# ethernet.net
KiCad netlist of a schematic drawn in Altium Designer
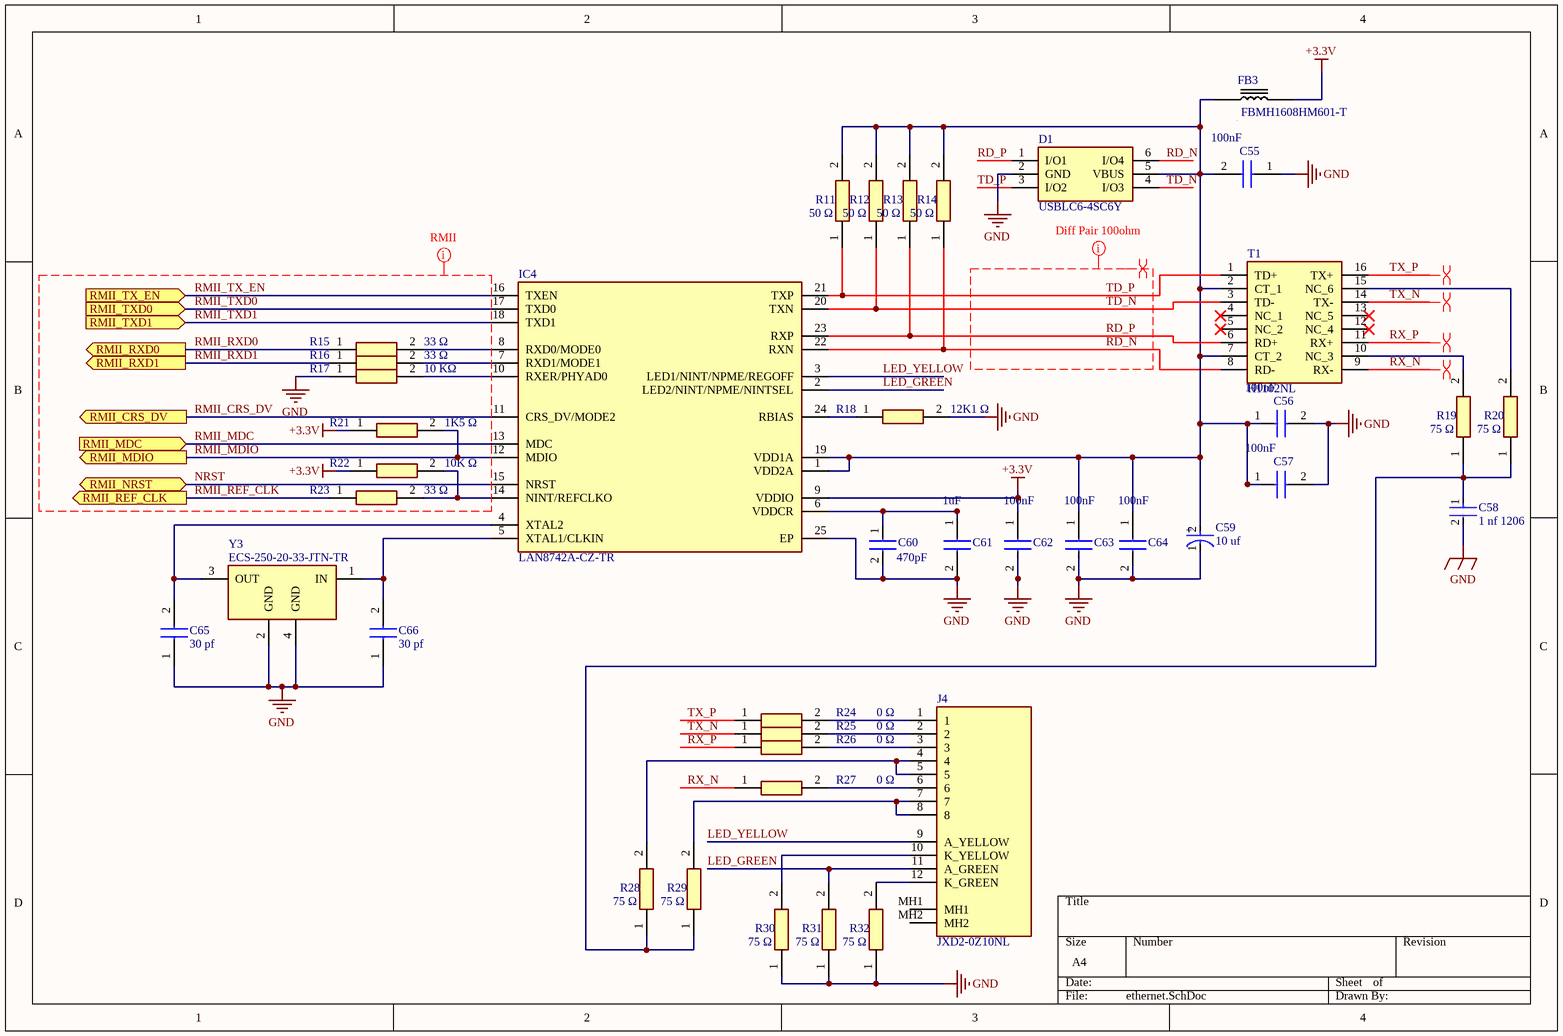
[diagram p0: ethernet.SchDoc]

(export (version "E")
  (design (tool "Eeschema 10.0.6"))
  (components
    (comp (ref "C55")
      (value "100nF")
      (footprint "PCB_library:CAPC1608X87N")
      (fields
        (field (name "MANUFACTURER_PART_NUMBER") "C0603C300J5GACTU")
        (field (name "MOUSER PART NUMBER") "80-C0603C300J5G")
        (field (name "MANUFACTURER") "TDK")
      )
      (libsource (lib "PCB_library") (part "C0603C300J5GACTU"))
    )
    (comp (ref "C56")
      (value "100nF")
      (footprint "PCB_library:CAPC1608X87N")
      (fields
        (field (name "MANUFACTURER_PART_NUMBER") "C0603C300J5GACTU")
        (field (name "MOUSER PART NUMBER") "80-C0603C300J5G")
        (field (name "MANUFACTURER") "TDK")
      )
      (libsource (lib "PCB_library") (part "C0603C300J5GACTU"))
    )
    (comp (ref "C57")
      (value "100nF")
      (footprint "PCB_library:CAPC1608X87N")
      (fields
        (field (name "MANUFACTURER_PART_NUMBER") "C0603C300J5GACTU")
        (field (name "MOUSER PART NUMBER") "80-C0603C300J5G")
        (field (name "MANUFACTURER") "TDK")
      )
      (libsource (lib "PCB_library") (part "C0603C300J5GACTU"))
    )
    (comp (ref "C58")
      (value "1 nf 1206")
      (footprint "FP-CC1206-0_3-1_45-IPC_C")
      (description "CAP CER 1000PF 2KV X7R 1206")
      (fields (field (name "TOLERANCE") "10%") (field (name "VOLTAGE") "2kV"))
      (libsource (lib "Altium Content Vault") (part "02cd4be3c70576c341d710602a673aa"))
    )
    (comp (ref "C59")
      (value "10 uf")
      (footprint "FP-T491D-MFG")
      (description "CAP TANT 10UF 10% 25V 2917")
      (fields (field (name "VOLTAGE") "25V") (field (name "TOLERANCE") "20%"))
      (libsource (lib "Altium Content Vault") (part "cf48714ba7e38822c1575c7ec0b6d1f"))
    )
    (comp (ref "C60")
      (value "470pF")
      (footprint "PCB_library:CAPC1005X55N")
      (fields
        (field (name "MANUFACTURER_PART_NUMBER") "CC0402KRX7R7BB104")
        (field (name "MOUSER PART NUMBER") "603-CC402KRX7R7BB104")
        (field (name "MANUFACTURER") "Murata")
      )
      (libsource (lib "PCB_library") (part "CC0402KRX7R7BB104"))
    )
    (comp (ref "C61")
      (value "1uF")
      (footprint "PCB_library:CAPC1608X87N")
      (fields
        (field (name "MANUFACTURER_PART_NUMBER") "C0603C300J5GACTU")
        (field (name "MOUSER PART NUMBER") "80-C0603C300J5G")
        (field (name "MANUFACTURER") "Kyocera AVX")
      )
      (libsource (lib "PCB_library") (part "C0603C300J5GACTU"))
    )
    (comp (ref "C62")
      (value "100nF")
      (footprint "PCB_library:CAPC1608X87N")
      (fields
        (field (name "MANUFACTURER_PART_NUMBER") "C0603C300J5GACTU")
        (field (name "MOUSER PART NUMBER") "80-C0603C300J5G")
        (field (name "MANUFACTURER") "TDK")
      )
      (libsource (lib "PCB_library") (part "C0603C300J5GACTU"))
    )
    (comp (ref "C63")
      (value "100nF")
      (footprint "PCB_library:CAPC1608X87N")
      (fields
        (field (name "MANUFACTURER_PART_NUMBER") "C0603C300J5GACTU")
        (field (name "MOUSER PART NUMBER") "80-C0603C300J5G")
        (field (name "MANUFACTURER") "TDK")
      )
      (libsource (lib "PCB_library") (part "C0603C300J5GACTU"))
    )
    (comp (ref "C64")
      (value "100nF")
      (footprint "PCB_library:CAPC1608X87N")
      (fields
        (field (name "MANUFACTURER_PART_NUMBER") "C0603C300J5GACTU")
        (field (name "MOUSER PART NUMBER") "80-C0603C300J5G")
        (field (name "MANUFACTURER") "TDK")
      )
      (libsource (lib "PCB_library") (part "C0603C300J5GACTU"))
    )
    (comp (ref "C65")
      (value "30 pf")
      (footprint "PCB_library:CAPC1608X87N")
      (fields
        (field (name "MANUFACTURER_PART_NUMBER") "C0603C300J5GACTU")
        (field (name "MOUSER PART NUMBER") "80-C0603C300J5G")
        (field (name "MANUFACTURER") "KEMET")
      )
      (libsource (lib "*") (part "C0603C300J5GACTU"))
    )
    (comp (ref "C66")
      (value "30 pf")
      (footprint "PCB_library:CAPC1608X87N")
      (fields
        (field (name "MANUFACTURER_PART_NUMBER") "C0603C300J5GACTU")
        (field (name "MOUSER PART NUMBER") "80-C0603C300J5G")
        (field (name "MANUFACTURER") "KEMET")
      )
      (libsource (lib "*") (part "C0603C300J5GACTU"))
    )
    (comp (ref "D1")
      (value "USBLC6-4SC6Y")
      (footprint "PCB_library:SOT95P280X145-6N")
      (description "Diode ESD (Uni-directional)")
      (fields (field (name "MOUSER PART NUMBER") "511-USBLC6-4SC6Y"))
      (libsource (lib "*") (part "USBLC6-4SC6Y"))
    )
    (comp (ref "FB3")
      (value "FBMH1608HM601-T")
      (footprint "PCB_library:BEADC1608X90N")
      (description "Ferrite Bead")
      (fields (field (name "MOUSER PART NUMBER") "963-FBMH1608HM601-T"))
      (libsource (lib "PCB_library") (part "FBMH1608HM601-T"))
    )
    (comp (ref "IC4")
      (value "LAN8742A-CZ-TR")
      (footprint "PCB_library:QFN50P400X400X100-25N-D")
      (description "Integrated Circuit")
      (fields (field (name "MOUSER PART NUMBER") "579-LAN8742A-CZ-TR"))
      (libsource (lib "PCB_library") (part "LAN8742A-CZ-TR"))
    )
    (comp (ref "J4")
      (value "JXD2-0Z10NL")
      (footprint "PCB_library:JXD20Z10NL")
      (description "Conn Jack 1PORT 100 Base-tx Pcb")
      (fields (field (name "MOUSER PART NUMBER") "673-JXD2-0Z10NL") (field (name "MANUFACTURER") "Pulse"))
      (libsource (lib "PCB_library") (part "JXD2-0Z10NL"))
    )
    (comp (ref "R11")
      (value "50 Ω")
      (footprint "RESC1005X35N")
      (description "Resistor")
      (fields
        (field (name "MANUFACTURER_PART_NUMBER") "CPF0402B100KE")
        (field (name "MOUSER PART NUMBER") "279-CPF0402B100KE")
      )
      (libsource (lib "*") (part "CPF0402B100KE"))
    )
    (comp (ref "R12")
      (value "50 Ω")
      (footprint "RESC1005X35N")
      (description "Resistor")
      (fields
        (field (name "MANUFACTURER_PART_NUMBER") "CPF0402B100KE")
        (field (name "MOUSER PART NUMBER") "279-CPF0402B100KE")
      )
      (libsource (lib "*") (part "CPF0402B100KE"))
    )
    (comp (ref "R13")
      (value "50 Ω")
      (footprint "RESC1005X35N")
      (description "Resistor")
      (fields
        (field (name "MANUFACTURER_PART_NUMBER") "CPF0402B100KE")
        (field (name "MOUSER PART NUMBER") "279-CPF0402B100KE")
      )
      (libsource (lib "*") (part "CPF0402B100KE"))
    )
    (comp (ref "R14")
      (value "50 Ω")
      (footprint "RESC1005X35N")
      (description "Resistor")
      (fields
        (field (name "MANUFACTURER_PART_NUMBER") "CPF0402B100KE")
        (field (name "MOUSER PART NUMBER") "279-CPF0402B100KE")
      )
      (libsource (lib "*") (part "CPF0402B100KE"))
    )
    (comp (ref "R15")
      (value "33 Ω")
      (footprint "RESC1005X35N")
      (description "Resistor")
      (fields
        (field (name "MANUFACTURER_PART_NUMBER") "CPF0402B100KE")
        (field (name "MOUSER PART NUMBER") "279-CPF0402B100KE")
      )
      (libsource (lib "") (part "CPF0402B100KE_1"))
    )
    (comp (ref "R16")
      (value "33 Ω")
      (footprint "RESC1005X35N")
      (description "Resistor")
      (fields
        (field (name "MANUFACTURER_PART_NUMBER") "CPF0402B100KE")
        (field (name "MOUSER PART NUMBER") "279-CPF0402B100KE")
      )
      (libsource (lib "") (part "CPF0402B100KE_1"))
    )
    (comp (ref "R17")
      (value "10 KΩ")
      (footprint "RESC1005X35N")
      (description "Resistor")
      (fields
        (field (name "MANUFACTURER_PART_NUMBER") "CPF0402B100KE")
        (field (name "MOUSER PART NUMBER") "279-CPF0402B100KE")
      )
      (libsource (lib "") (part "CPF0402B100KE_1"))
    )
    (comp (ref "R18")
      (value "12K1 Ω")
      (footprint "RESC1005X35N")
      (description "Resistor")
      (fields
        (field (name "MANUFACTURER_PART_NUMBER") "CPF0402B100KE")
        (field (name "MOUSER PART NUMBER") "279-CPF0402B100KE")
      )
      (libsource (lib "") (part "CPF0402B100KE_1"))
    )
    (comp (ref "R19")
      (value "75 Ω")
      (footprint "RESC1005X35N")
      (description "Resistor")
      (fields
        (field (name "MANUFACTURER_PART_NUMBER") "CPF0402B100KE")
        (field (name "MOUSER PART NUMBER") "279-CPF0402B100KE")
      )
      (libsource (lib "*") (part "CPF0402B100KE"))
    )
    (comp (ref "R20")
      (value "75 Ω")
      (footprint "RESC1005X35N")
      (description "Resistor")
      (fields
        (field (name "MANUFACTURER_PART_NUMBER") "CPF0402B100KE")
        (field (name "MOUSER PART NUMBER") "279-CPF0402B100KE")
      )
      (libsource (lib "*") (part "CPF0402B100KE"))
    )
    (comp (ref "R21")
      (value "1K5 Ω")
      (footprint "RESC1005X35N")
      (description "Resistor")
      (fields
        (field (name "MANUFACTURER_PART_NUMBER") "CPF0402B100KE")
        (field (name "MOUSER PART NUMBER") "279-CPF0402B100KE")
      )
      (libsource (lib "") (part "CPF0402B100KE_1"))
    )
    (comp (ref "R22")
      (value "10K Ω")
      (footprint "RESC1005X35N")
      (description "Resistor")
      (fields
        (field (name "MANUFACTURER_PART_NUMBER") "CPF0402B100KE")
        (field (name "MOUSER PART NUMBER") "279-CPF0402B100KE")
      )
      (libsource (lib "") (part "CPF0402B100KE_1"))
    )
    (comp (ref "R23")
      (value "33 Ω")
      (footprint "RESC1005X35N")
      (description "Resistor")
      (fields
        (field (name "MANUFACTURER_PART_NUMBER") "CPF0402B100KE")
        (field (name "MOUSER PART NUMBER") "279-CPF0402B100KE")
      )
      (libsource (lib "") (part "CPF0402B100KE_1"))
    )
    (comp (ref "R24")
      (value "0 Ω")
      (footprint "RESC1005X35N")
      (description "Resistor")
      (fields
        (field (name "MANUFACTURER_PART_NUMBER") "CPF0402B100KE")
        (field (name "MOUSER PART NUMBER") "279-CPF0402B100KE")
      )
      (libsource (lib "") (part "CPF0402B100KE_1"))
    )
    (comp (ref "R25")
      (value "0 Ω")
      (footprint "RESC1005X35N")
      (description "Resistor")
      (fields
        (field (name "MANUFACTURER_PART_NUMBER") "CPF0402B100KE")
        (field (name "MOUSER PART NUMBER") "279-CPF0402B100KE")
      )
      (libsource (lib "") (part "CPF0402B100KE_1"))
    )
    (comp (ref "R26")
      (value "0 Ω")
      (footprint "RESC1005X35N")
      (description "Resistor")
      (fields
        (field (name "MANUFACTURER_PART_NUMBER") "CPF0402B100KE")
        (field (name "MOUSER PART NUMBER") "279-CPF0402B100KE")
      )
      (libsource (lib "") (part "CPF0402B100KE_1"))
    )
    (comp (ref "R27")
      (value "0 Ω")
      (footprint "RESC1005X35N")
      (description "Resistor")
      (fields
        (field (name "MANUFACTURER_PART_NUMBER") "CPF0402B100KE")
        (field (name "MOUSER PART NUMBER") "279-CPF0402B100KE")
      )
      (libsource (lib "") (part "CPF0402B100KE_1"))
    )
    (comp (ref "R28")
      (value "75 Ω")
      (footprint "RESC1005X35N")
      (description "Resistor")
      (fields
        (field (name "MANUFACTURER_PART_NUMBER") "CPF0402B100KE")
        (field (name "MOUSER PART NUMBER") "279-CPF0402B100KE")
      )
      (libsource (lib "*") (part "CPF0402B100KE"))
    )
    (comp (ref "R29")
      (value "75 Ω")
      (footprint "RESC1005X35N")
      (description "Resistor")
      (fields
        (field (name "MANUFACTURER_PART_NUMBER") "CPF0402B100KE")
        (field (name "MOUSER PART NUMBER") "279-CPF0402B100KE")
      )
      (libsource (lib "*") (part "CPF0402B100KE"))
    )
    (comp (ref "R30")
      (value "75 Ω")
      (footprint "RESC1005X35N")
      (description "Resistor")
      (fields
        (field (name "MANUFACTURER_PART_NUMBER") "CPF0402B100KE")
        (field (name "MOUSER PART NUMBER") "279-CPF0402B100KE")
      )
      (libsource (lib "*") (part "CPF0402B100KE"))
    )
    (comp (ref "R31")
      (value "75 Ω")
      (footprint "RESC1005X35N")
      (description "Resistor")
      (fields
        (field (name "MANUFACTURER_PART_NUMBER") "CPF0402B100KE")
        (field (name "MOUSER PART NUMBER") "279-CPF0402B100KE")
      )
      (libsource (lib "*") (part "CPF0402B100KE"))
    )
    (comp (ref "R32")
      (value "75 Ω")
      (footprint "RESC1005X35N")
      (description "Resistor")
      (fields
        (field (name "MANUFACTURER_PART_NUMBER") "CPF0402B100KE")
        (field (name "MOUSER PART NUMBER") "279-CPF0402B100KE")
      )
      (libsource (lib "*") (part "CPF0402B100KE"))
    )
    (comp (ref "T1")
      (value "H1102NL")
      (footprint "PCB_library:SOIC127P940X597-16N")
      (description "Transformer")
      (fields (field (name "MOUSER PART NUMBER") "673-H1102NL"))
      (libsource (lib "*") (part "H1102NL"))
    )
    (comp (ref "Y3")
      (value "ECS-250-20-33-JTN-TR")
      (footprint "ECS-250-20-33-JTN-TR")
      (description "Crystal or Oscillator")
      (fields (field (name "MANUFACTURER_PART_NUMBER") "CO4605-100.000-T-TR"))
      (libsource (lib "PCB_library") (part "ECS-250-20-33-JTN-TR"))
    )
  )
  (nets
    (net (code "1") (name "+3.3V") (class "Default")
      (node (ref "C62") (pin "1") (pinfunction "1_1") (pintype "passive"))
      (node (ref "FB3") (pin "2") (pinfunction "2_2") (pintype "passive"))
      (node (ref "IC4") (pin "9") (pinfunction "VDDIO_9") (pintype "passive"))
      (node (ref "R21") (pin "1") (pinfunction "1_1") (pintype "passive"))
      (node (ref "R22") (pin "1") (pinfunction "1_1") (pintype "passive"))
    )
    (net (code "2") (name "/LED_GREEN") (class "Default")
      (node (ref "IC4") (pin "2") (pinfunction "LED2/NINT/NPME/NINTSEL_2") (pintype "passive"))
      (node (ref "J4") (pin "11") (pinfunction "A_GREEN_11") (pintype "passive"))
      (node (ref "R31") (pin "2") (pinfunction "2_2") (pintype "passive"))
    )
    (net (code "3") (name "/LED_YELLOW") (class "Default")
      (node (ref "IC4") (pin "3") (pinfunction "LED1/NINT/NPME/REGOFF_3") (pintype "passive"))
      (node (ref "J4") (pin "9") (pinfunction "A_YELLOW_9") (pintype "passive"))
    )
    (net (code "4") (name "/NRST") (class "Default")
      (node (ref "IC4") (pin "15") (pinfunction "NRST_15") (pintype "passive"))
    )
    (net (code "5") (name "/RD_N") (class "Default")
      (node (ref "D1") (pin "6") (pinfunction "I/O4_6") (pintype "passive"))
      (node (ref "IC4") (pin "22") (pinfunction "RXN_22") (pintype "passive"))
      (node (ref "R14") (pin "1") (pinfunction "1_1") (pintype "passive"))
      (node (ref "T1") (pin "8") (pinfunction "RD-_8") (pintype "passive"))
    )
    (net (code "6") (name "/RD_P") (class "Default")
      (node (ref "D1") (pin "1") (pinfunction "I/O1_1") (pintype "passive"))
      (node (ref "IC4") (pin "23") (pinfunction "RXP_23") (pintype "passive"))
      (node (ref "R13") (pin "1") (pinfunction "1_1") (pintype "passive"))
      (node (ref "T1") (pin "6") (pinfunction "RD+_6") (pintype "passive"))
    )
    (net (code "7") (name "/RMII_CRS_DV") (class "Default")
      (node (ref "IC4") (pin "11") (pinfunction "CRS_DV/MODE2_11") (pintype "passive"))
    )
    (net (code "8") (name "/RMII_MDC") (class "Default")
      (node (ref "IC4") (pin "13") (pinfunction "MDC_13") (pintype "passive"))
    )
    (net (code "9") (name "/RMII_MDIO") (class "Default")
      (node (ref "IC4") (pin "12") (pinfunction "MDIO_12") (pintype "passive"))
      (node (ref "R21") (pin "2") (pinfunction "2_2") (pintype "passive"))
    )
    (net (code "10") (name "/RMII_REF_CLK") (class "Default")
      (node (ref "R23") (pin "1") (pinfunction "1_1") (pintype "passive"))
    )
    (net (code "11") (name "/RMII_RXD0") (class "Default")
      (node (ref "R15") (pin "1") (pinfunction "1_1") (pintype "passive"))
    )
    (net (code "12") (name "/RMII_RXD1") (class "Default")
      (node (ref "R16") (pin "1") (pinfunction "1_1") (pintype "passive"))
    )
    (net (code "13") (name "/RMII_TXD0") (class "Default")
      (node (ref "IC4") (pin "17") (pinfunction "TXD0_17") (pintype "passive"))
    )
    (net (code "14") (name "/RMII_TXD1") (class "Default")
      (node (ref "IC4") (pin "18") (pinfunction "TXD1_18") (pintype "passive"))
    )
    (net (code "15") (name "/RMII_TX_EN") (class "Default")
      (node (ref "IC4") (pin "16") (pinfunction "TXEN_16") (pintype "passive"))
    )
    (net (code "16") (name "/RX_N") (class "Default")
      (node (ref "R27") (pin "1") (pinfunction "1_1") (pintype "passive"))
      (node (ref "T1") (pin "9") (pinfunction "RX-_9") (pintype "passive"))
    )
    (net (code "17") (name "/RX_P") (class "Default")
      (node (ref "R26") (pin "1") (pinfunction "1_1") (pintype "passive"))
      (node (ref "T1") (pin "11") (pinfunction "RX+_11") (pintype "passive"))
    )
    (net (code "18") (name "/TD_N") (class "Default")
      (node (ref "D1") (pin "4") (pinfunction "I/O3_4") (pintype "passive"))
      (node (ref "IC4") (pin "20") (pinfunction "TXN_20") (pintype "passive"))
      (node (ref "R12") (pin "1") (pinfunction "1_1") (pintype "passive"))
      (node (ref "T1") (pin "3") (pinfunction "TD-_3") (pintype "passive"))
    )
    (net (code "19") (name "/TD_P") (class "Default")
      (node (ref "D1") (pin "3") (pinfunction "I/O2_3") (pintype "passive"))
      (node (ref "IC4") (pin "21") (pinfunction "TXP_21") (pintype "passive"))
      (node (ref "R11") (pin "1") (pinfunction "1_1") (pintype "passive"))
      (node (ref "T1") (pin "1") (pinfunction "TD+_1") (pintype "passive"))
    )
    (net (code "20") (name "/TX_N") (class "Default")
      (node (ref "R25") (pin "1") (pinfunction "1_1") (pintype "passive"))
      (node (ref "T1") (pin "14") (pinfunction "TX-_14") (pintype "passive"))
    )
    (net (code "21") (name "/TX_P") (class "Default")
      (node (ref "R24") (pin "1") (pinfunction "1_1") (pintype "passive"))
      (node (ref "T1") (pin "16") (pinfunction "TX+_16") (pintype "passive"))
    )
    (net (code "22") (name "GND") (class "Default")
      (node (ref "C55") (pin "1") (pinfunction "1_1") (pintype "passive"))
      (node (ref "C56") (pin "2") (pinfunction "2_2") (pintype "passive"))
      (node (ref "C57") (pin "2") (pinfunction "2_2") (pintype "passive"))
      (node (ref "C58") (pin "2") (pinfunction "2_2") (pintype "passive"))
      (node (ref "C59") (pin "1") (pinfunction "C_1") (pintype "passive"))
      (node (ref "C60") (pin "2") (pinfunction "2_2") (pintype "passive"))
      (node (ref "C61") (pin "2") (pinfunction "2_2") (pintype "passive"))
      (node (ref "C62") (pin "2") (pinfunction "2_2") (pintype "passive"))
      (node (ref "C63") (pin "2") (pinfunction "2_2") (pintype "passive"))
      (node (ref "C64") (pin "2") (pinfunction "2_2") (pintype "passive"))
      (node (ref "C65") (pin "1") (pinfunction "1_1") (pintype "passive"))
      (node (ref "C66") (pin "1") (pinfunction "1_1") (pintype "passive"))
      (node (ref "D1") (pin "2") (pinfunction "GND_2") (pintype "passive"))
      (node (ref "IC4") (pin "25") (pinfunction "EP_25") (pintype "passive"))
      (node (ref "R17") (pin "1") (pinfunction "1_1") (pintype "passive"))
      (node (ref "R18") (pin "2") (pinfunction "2_2") (pintype "passive"))
      (node (ref "R30") (pin "1") (pinfunction "1_1") (pintype "passive"))
      (node (ref "R31") (pin "1") (pinfunction "1_1") (pintype "passive"))
      (node (ref "R32") (pin "1") (pinfunction "1_1") (pintype "passive"))
      (node (ref "Y3") (pin "2") (pinfunction "GND_2") (pintype "passive"))
      (node (ref "Y3") (pin "4") (pinfunction "GND_4") (pintype "passive"))
    )
    (net (code "23") (name "Net-(C58-Pad1)") (class "Default")
      (node (ref "C58") (pin "1") (pinfunction "1_1") (pintype "passive"))
      (node (ref "R19") (pin "1") (pinfunction "1_1") (pintype "passive"))
      (node (ref "R20") (pin "1") (pinfunction "1_1") (pintype "passive"))
      (node (ref "R28") (pin "1") (pinfunction "1_1") (pintype "passive"))
      (node (ref "R29") (pin "1") (pinfunction "1_1") (pintype "passive"))
    )
    (net (code "24") (name "Net-(C59-A)") (class "Default")
      (node (ref "C55") (pin "2") (pinfunction "2_2") (pintype "passive"))
      (node (ref "C56") (pin "1") (pinfunction "1_1") (pintype "passive"))
      (node (ref "C57") (pin "1") (pinfunction "1_1") (pintype "passive"))
      (node (ref "C59") (pin "2") (pinfunction "A_2") (pintype "passive"))
      (node (ref "C63") (pin "1") (pinfunction "1_1") (pintype "passive"))
      (node (ref "C64") (pin "1") (pinfunction "1_1") (pintype "passive"))
      (node (ref "D1") (pin "5") (pinfunction "VBUS_5") (pintype "passive"))
      (node (ref "FB3") (pin "1") (pinfunction "1_1") (pintype "passive"))
      (node (ref "IC4") (pin "1") (pinfunction "VDD2A_1") (pintype "passive"))
      (node (ref "IC4") (pin "19") (pinfunction "VDD1A_19") (pintype "passive"))
      (node (ref "R11") (pin "2") (pinfunction "2_2") (pintype "passive"))
      (node (ref "R12") (pin "2") (pinfunction "2_2") (pintype "passive"))
      (node (ref "R13") (pin "2") (pinfunction "2_2") (pintype "passive"))
      (node (ref "R14") (pin "2") (pinfunction "2_2") (pintype "passive"))
      (node (ref "T1") (pin "2") (pinfunction "CT_1_2") (pintype "passive"))
      (node (ref "T1") (pin "7") (pinfunction "CT_2_7") (pintype "passive"))
    )
    (net (code "25") (name "Net-(IC4-NINT{slash}REFCLKO)") (class "Default")
      (node (ref "IC4") (pin "14") (pinfunction "NINT/REFCLKO_14") (pintype "passive"))
      (node (ref "R22") (pin "2") (pinfunction "2_2") (pintype "passive"))
      (node (ref "R23") (pin "2") (pinfunction "2_2") (pintype "passive"))
    )
    (net (code "26") (name "Net-(IC4-RBIAS)") (class "Default")
      (node (ref "IC4") (pin "24") (pinfunction "RBIAS_24") (pintype "passive"))
      (node (ref "R18") (pin "1") (pinfunction "1_1") (pintype "passive"))
    )
    (net (code "27") (name "Net-(IC4-RXD0{slash}MODE0)") (class "Default")
      (node (ref "IC4") (pin "8") (pinfunction "RXD0/MODE0_8") (pintype "passive"))
      (node (ref "R15") (pin "2") (pinfunction "2_2") (pintype "passive"))
    )
    (net (code "28") (name "Net-(IC4-RXD1{slash}MODE1)") (class "Default")
      (node (ref "IC4") (pin "7") (pinfunction "RXD1/MODE1_7") (pintype "passive"))
      (node (ref "R16") (pin "2") (pinfunction "2_2") (pintype "passive"))
    )
    (net (code "29") (name "Net-(IC4-RXER{slash}PHYAD0)") (class "Default")
      (node (ref "IC4") (pin "10") (pinfunction "RXER/PHYAD0_10") (pintype "passive"))
      (node (ref "R17") (pin "2") (pinfunction "2_2") (pintype "passive"))
    )
    (net (code "30") (name "Net-(IC4-VDDCR)") (class "Default")
      (node (ref "C60") (pin "1") (pinfunction "1_1") (pintype "passive"))
      (node (ref "C61") (pin "1") (pinfunction "1_1") (pintype "passive"))
      (node (ref "IC4") (pin "6") (pinfunction "VDDCR_6") (pintype "passive"))
    )
    (net (code "31") (name "Net-(IC4-XTAL1{slash}CLKIN)") (class "Default")
      (node (ref "C66") (pin "2") (pinfunction "2_2") (pintype "passive"))
      (node (ref "IC4") (pin "5") (pinfunction "XTAL1/CLKIN_5") (pintype "passive"))
      (node (ref "Y3") (pin "1") (pinfunction "IN_1") (pintype "passive"))
    )
    (net (code "32") (name "Net-(IC4-XTAL2)") (class "Default")
      (node (ref "C65") (pin "2") (pinfunction "2_2") (pintype "passive"))
      (node (ref "IC4") (pin "4") (pinfunction "XTAL2_4") (pintype "passive"))
      (node (ref "Y3") (pin "3") (pinfunction "OUT_3") (pintype "passive"))
    )
    (net (code "33") (name "Net-(J4-K_GREEN)") (class "Default")
      (node (ref "J4") (pin "12") (pinfunction "K_GREEN_12") (pintype "passive"))
      (node (ref "R32") (pin "2") (pinfunction "2_2") (pintype "passive"))
    )
    (net (code "34") (name "Net-(J4-K_YELLOW)") (class "Default")
      (node (ref "J4") (pin "10") (pinfunction "K_YELLOW_10") (pintype "passive"))
      (node (ref "R30") (pin "2") (pinfunction "2_2") (pintype "passive"))
    )
    (net (code "35") (name "Net-(J4-Pad1)") (class "Default")
      (node (ref "J4") (pin "1") (pinfunction "1_1") (pintype "passive"))
      (node (ref "R24") (pin "2") (pinfunction "2_2") (pintype "passive"))
    )
    (net (code "36") (name "Net-(J4-Pad2)") (class "Default")
      (node (ref "J4") (pin "2") (pinfunction "2_2") (pintype "passive"))
      (node (ref "R25") (pin "2") (pinfunction "2_2") (pintype "passive"))
    )
    (net (code "37") (name "Net-(J4-Pad3)") (class "Default")
      (node (ref "J4") (pin "3") (pinfunction "3_3") (pintype "passive"))
      (node (ref "R26") (pin "2") (pinfunction "2_2") (pintype "passive"))
    )
    (net (code "38") (name "Net-(J4-Pad4)") (class "Default")
      (node (ref "J4") (pin "4") (pinfunction "4_4") (pintype "passive"))
      (node (ref "J4") (pin "5") (pinfunction "5_5") (pintype "passive"))
      (node (ref "R28") (pin "2") (pinfunction "2_2") (pintype "passive"))
    )
    (net (code "39") (name "Net-(J4-Pad6)") (class "Default")
      (node (ref "J4") (pin "6") (pinfunction "6_6") (pintype "passive"))
      (node (ref "R27") (pin "2") (pinfunction "2_2") (pintype "passive"))
    )
    (net (code "40") (name "Net-(J4-Pad7)") (class "Default")
      (node (ref "J4") (pin "7") (pinfunction "7_7") (pintype "passive"))
      (node (ref "J4") (pin "8") (pinfunction "8_8") (pintype "passive"))
      (node (ref "R29") (pin "2") (pinfunction "2_2") (pintype "passive"))
    )
    (net (code "41") (name "Net-(T1-NC_3)") (class "Default")
      (node (ref "R19") (pin "2") (pinfunction "2_2") (pintype "passive"))
      (node (ref "T1") (pin "10") (pinfunction "NC_3_10") (pintype "passive"))
    )
    (net (code "42") (name "Net-(T1-NC_6)") (class "Default")
      (node (ref "R20") (pin "2") (pinfunction "2_2") (pintype "passive"))
      (node (ref "T1") (pin "15") (pinfunction "NC_6_15") (pintype "passive"))
    )
    (net (code "43") (name "unconnected-(J4-PadMH1)") (class "Default")
      (node (ref "J4") (pin "MH1") (pinfunction "MH1_MH1") (pintype "passive"))
    )
    (net (code "44") (name "unconnected-(J4-PadMH2)") (class "Default")
      (node (ref "J4") (pin "MH2") (pinfunction "MH2_MH2") (pintype "passive"))
    )
    (net (code "45") (name "unconnected-(T1-NC_1-Pad4)") (class "Default")
      (node (ref "T1") (pin "4") (pinfunction "NC_1_4") (pintype "passive+no_connect"))
    )
    (net (code "46") (name "unconnected-(T1-NC_2-Pad5)") (class "Default")
      (node (ref "T1") (pin "5") (pinfunction "NC_2_5") (pintype "passive+no_connect"))
    )
    (net (code "47") (name "unconnected-(T1-NC_4-Pad12)") (class "Default")
      (node (ref "T1") (pin "12") (pinfunction "NC_4_12") (pintype "passive+no_connect"))
    )
    (net (code "48") (name "unconnected-(T1-NC_5-Pad13)") (class "Default")
      (node (ref "T1") (pin "13") (pinfunction "NC_5_13") (pintype "passive+no_connect"))
    )
  )
)
